# Interconnect_board_v1p2.net
KiCad netlist of a schematic drawn in EAGLE
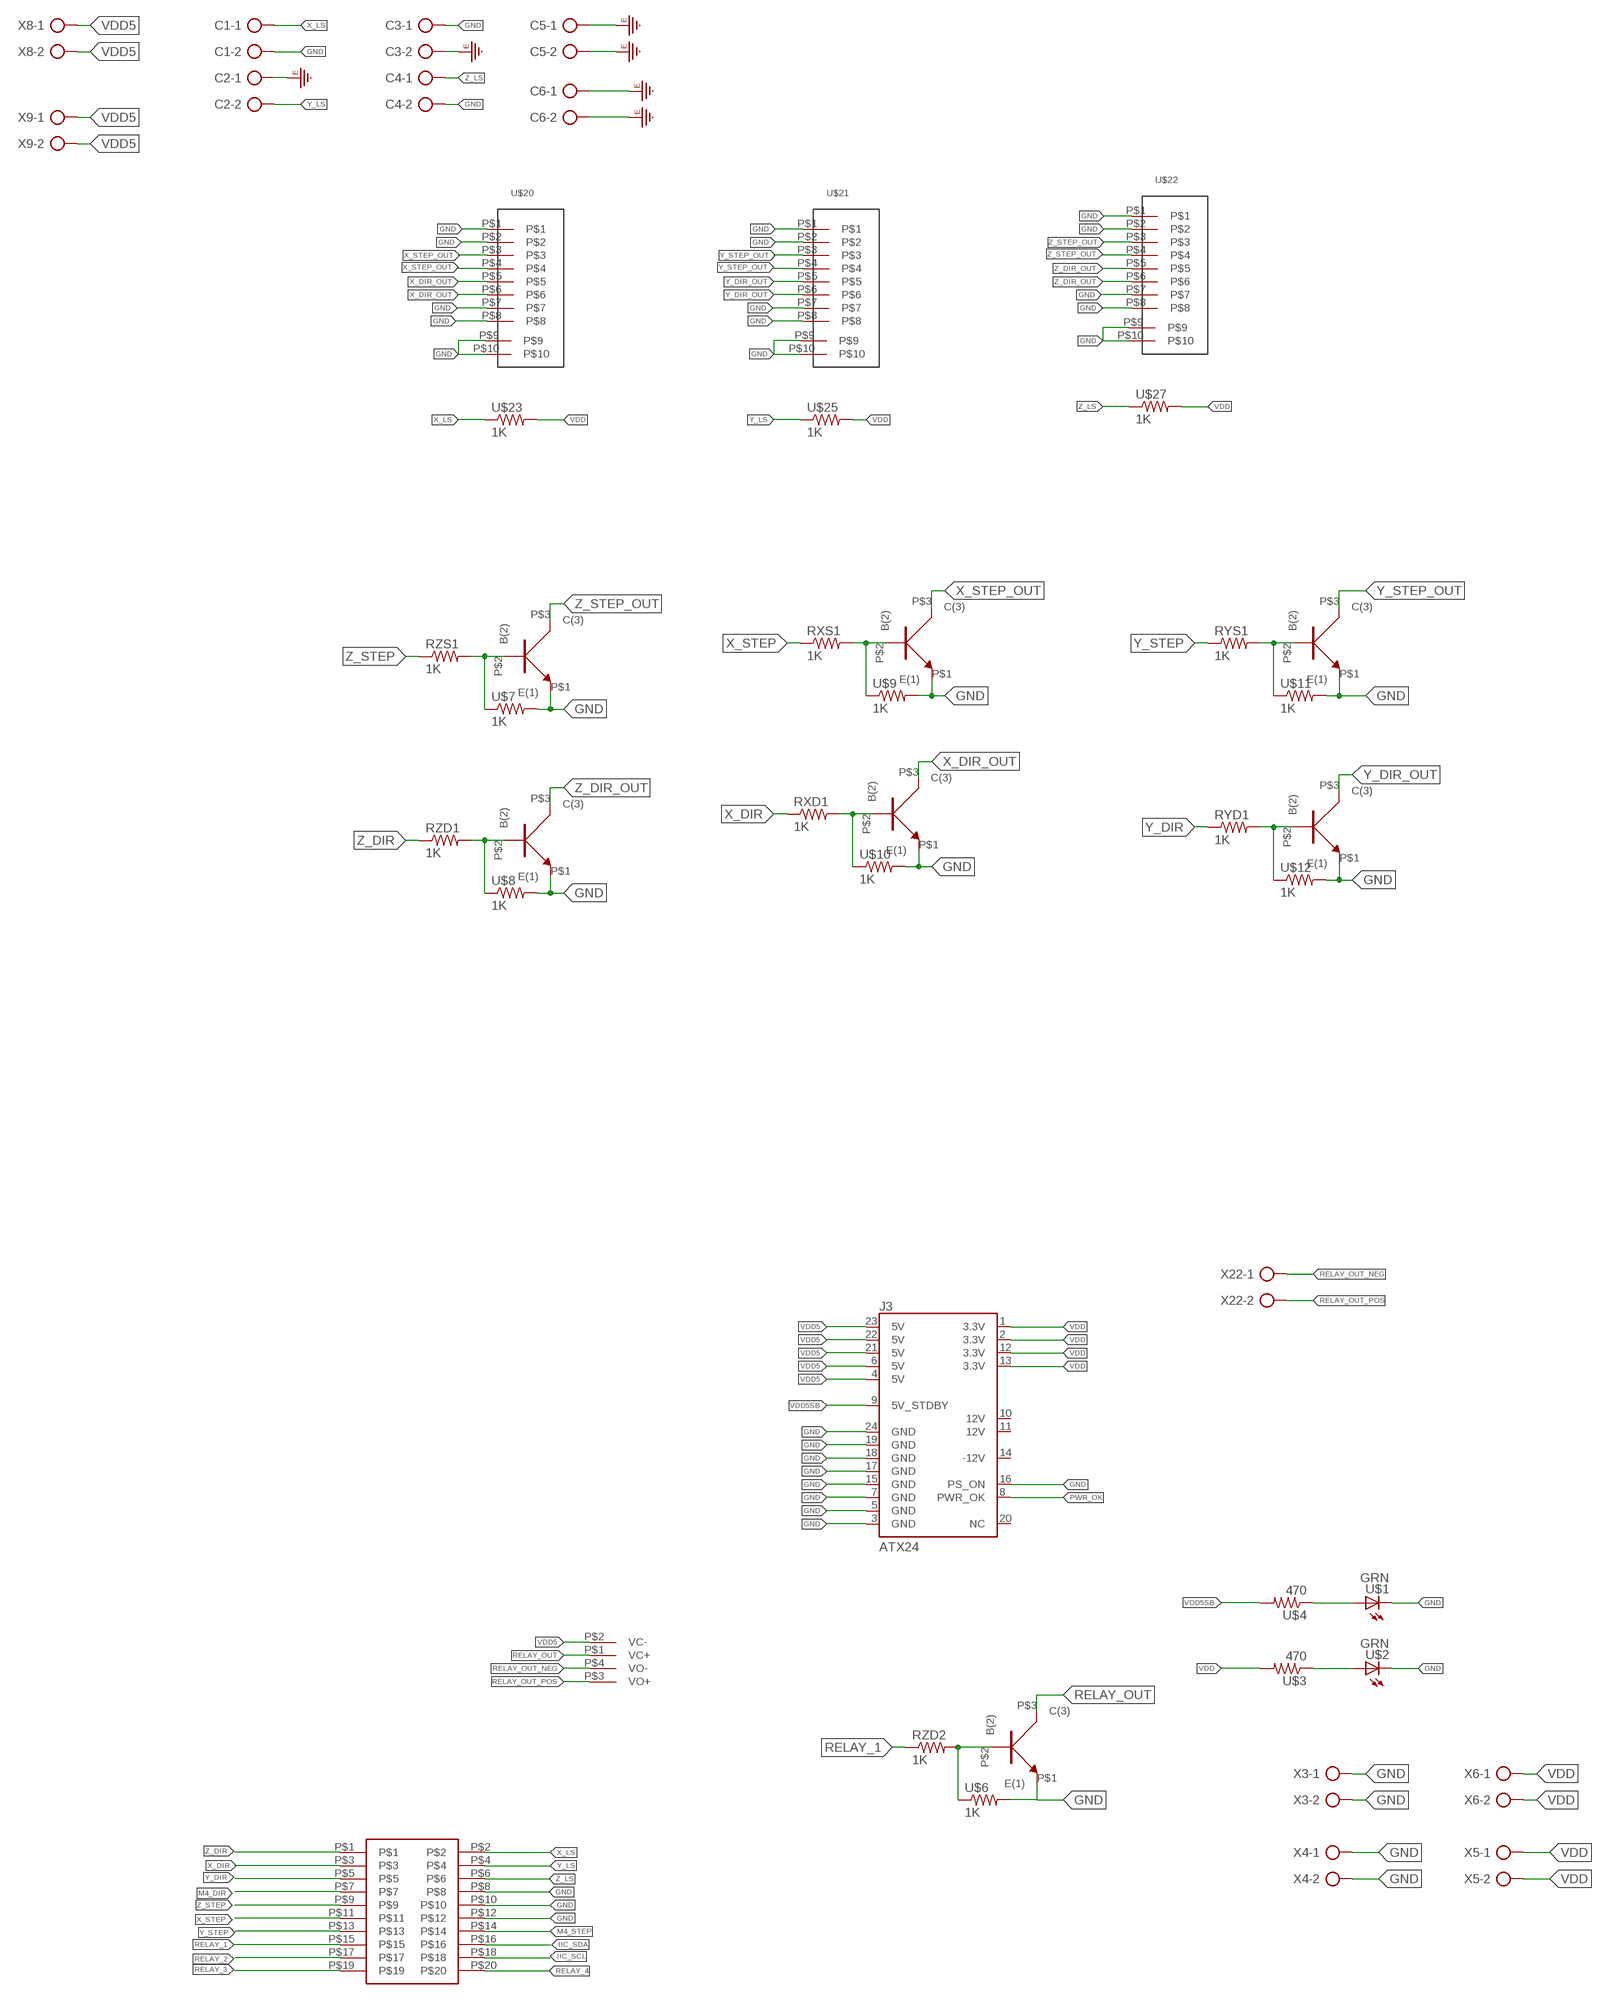
[diagram p0: schematic, sheet 1]

(export (version "E")
  (design (tool "Eeschema 10.0.6"))
  (components
    (comp (ref "C1")
      (value "AK300/2")
      (footprint "eagle-import:AK300_2")
      (libsource (lib "eagle-import") (part "AK300/2"))
    )
    (comp (ref "C2")
      (value "AK300/2")
      (footprint "eagle-import:AK300_2")
      (libsource (lib "eagle-import") (part "AK300/2"))
    )
    (comp (ref "C3")
      (value "AK300/2")
      (footprint "eagle-import:AK300_2")
      (libsource (lib "eagle-import") (part "AK300/2"))
    )
    (comp (ref "C4")
      (value "AK300/2")
      (footprint "eagle-import:AK300_2")
      (libsource (lib "eagle-import") (part "AK300/2"))
    )
    (comp (ref "C5")
      (value "AK300/2")
      (footprint "eagle-import:AK300_2")
      (libsource (lib "eagle-import") (part "AK300/2"))
    )
    (comp (ref "C6")
      (value "AK300/2")
      (footprint "eagle-import:AK300_2")
      (libsource (lib "eagle-import") (part "AK300/2"))
    )
    (comp (ref "J3")
      (value "ATX24")
      (footprint "eagle-import:ATX24_STRAIGHT")
      (libsource (lib "eagle-import") (part "ATX24"))
    )
    (comp (ref "RXD1")
      (value "R_0805_1K")
      (footprint "eagle-import:R_0805_1K")
      (libsource (lib "eagle-import") (part "R_0805_1K"))
    )
    (comp (ref "RXS1")
      (value "R_0805_1K")
      (footprint "eagle-import:R_0805_1K")
      (libsource (lib "eagle-import") (part "R_0805_1K"))
    )
    (comp (ref "RYD1")
      (value "R_0805_1K")
      (footprint "eagle-import:R_0805_1K")
      (libsource (lib "eagle-import") (part "R_0805_1K"))
    )
    (comp (ref "RYS1")
      (value "R_0805_1K")
      (footprint "eagle-import:R_0805_1K")
      (libsource (lib "eagle-import") (part "R_0805_1K"))
    )
    (comp (ref "RZD1")
      (value "R_0805_1K")
      (footprint "eagle-import:R_0805_1K")
      (libsource (lib "eagle-import") (part "R_0805_1K"))
    )
    (comp (ref "RZD2")
      (value "R_0805_1K")
      (footprint "eagle-import:R_0805_1K")
      (libsource (lib "eagle-import") (part "R_0805_1K"))
    )
    (comp (ref "RZS1")
      (value "R_0805_1K")
      (footprint "eagle-import:R_0805_1K")
      (libsource (lib "eagle-import") (part "R_0805_1K"))
    )
    (comp (ref "U$1")
      (value "LED_0805_GREEN")
      (footprint "eagle-import:LED_0805_GREEN")
      (libsource (lib "eagle-import") (part "LED_0805_GREEN"))
    )
    (comp (ref "U$2")
      (value "LED_0805_GREEN")
      (footprint "eagle-import:LED_0805_GREEN")
      (libsource (lib "eagle-import") (part "LED_0805_GREEN"))
    )
    (comp (ref "U$3")
      (value "R_0805_470")
      (footprint "eagle-import:R_0805_470")
      (libsource (lib "eagle-import") (part "R_0805_470"))
    )
    (comp (ref "U$4")
      (value "R_0805_470")
      (footprint "eagle-import:R_0805_470")
      (libsource (lib "eagle-import") (part "R_0805_470"))
    )
    (comp (ref "U$5")
      (value "RELAY_KYOTO_KF0604D")
      (footprint "eagle-import:RELAY_KYOTO_KF0604D")
      (libsource (lib "eagle-import") (part "RELAY_KYOTO_KF0604D"))
    )
    (comp (ref "U$6")
      (value "R_0805_1K")
      (footprint "eagle-import:R_0805_1K")
      (libsource (lib "eagle-import") (part "R_0805_1K"))
    )
    (comp (ref "U$7")
      (value "R_0805_1K")
      (footprint "eagle-import:R_0805_1K")
      (libsource (lib "eagle-import") (part "R_0805_1K"))
    )
    (comp (ref "U$8")
      (value "R_0805_1K")
      (footprint "eagle-import:R_0805_1K")
      (libsource (lib "eagle-import") (part "R_0805_1K"))
    )
    (comp (ref "U$9")
      (value "R_0805_1K")
      (footprint "eagle-import:R_0805_1K")
      (libsource (lib "eagle-import") (part "R_0805_1K"))
    )
    (comp (ref "U$10")
      (value "R_0805_1K")
      (footprint "eagle-import:R_0805_1K")
      (libsource (lib "eagle-import") (part "R_0805_1K"))
    )
    (comp (ref "U$11")
      (value "R_0805_1K")
      (footprint "eagle-import:R_0805_1K")
      (libsource (lib "eagle-import") (part "R_0805_1K"))
    )
    (comp (ref "U$12")
      (value "R_0805_1K")
      (footprint "eagle-import:R_0805_1K")
      (libsource (lib "eagle-import") (part "R_0805_1K"))
    )
    (comp (ref "U$13")
      (value "TRANS_NPN")
      (footprint "eagle-import:TO_92_STRAIGHT")
      (libsource (lib "eagle-import") (part "TRANS_NPN"))
    )
    (comp (ref "U$14")
      (value "TRANS_NPN")
      (footprint "eagle-import:TO_92_STRAIGHT")
      (libsource (lib "eagle-import") (part "TRANS_NPN"))
    )
    (comp (ref "U$15")
      (value "TRANS_NPN")
      (footprint "eagle-import:TO_92_STRAIGHT")
      (libsource (lib "eagle-import") (part "TRANS_NPN"))
    )
    (comp (ref "U$16")
      (value "TRANS_NPN")
      (footprint "eagle-import:TO_92_STRAIGHT")
      (libsource (lib "eagle-import") (part "TRANS_NPN"))
    )
    (comp (ref "U$17")
      (value "TRANS_NPN")
      (footprint "eagle-import:TO_92_STRAIGHT")
      (libsource (lib "eagle-import") (part "TRANS_NPN"))
    )
    (comp (ref "U$18")
      (value "TRANS_NPN")
      (footprint "eagle-import:TO_92_STRAIGHT")
      (libsource (lib "eagle-import") (part "TRANS_NPN"))
    )
    (comp (ref "U$19")
      (value "TRANS_NPN")
      (footprint "eagle-import:TO_92_STRAIGHT")
      (libsource (lib "eagle-import") (part "TRANS_NPN"))
    )
    (comp (ref "U$20")
      (value "RJ45_SMTRJ")
      (footprint "eagle-import:RJ45_SMT")
      (libsource (lib "eagle-import") (part "RJ45_SMTRJ"))
    )
    (comp (ref "U$21")
      (value "RJ45_SMTRJ")
      (footprint "eagle-import:RJ45_SMT")
      (libsource (lib "eagle-import") (part "RJ45_SMTRJ"))
    )
    (comp (ref "U$22")
      (value "RJ45_SMTRJ")
      (footprint "eagle-import:RJ45_SMT")
      (libsource (lib "eagle-import") (part "RJ45_SMTRJ"))
    )
    (comp (ref "U$23")
      (value "R_0805_1K")
      (footprint "eagle-import:R_0805_1K")
      (libsource (lib "eagle-import") (part "R_0805_1K"))
    )
    (comp (ref "U$25")
      (value "R_0805_1K")
      (footprint "eagle-import:R_0805_1K")
      (libsource (lib "eagle-import") (part "R_0805_1K"))
    )
    (comp (ref "U$26")
      (value "2_X_10_HEADER_GENERIC")
      (footprint "eagle-import:2_X_10_.1_INCH")
      (libsource (lib "eagle-import") (part "2_X_10_HEADER_GENERIC"))
    )
    (comp (ref "U$27")
      (value "R_0805_1K")
      (footprint "eagle-import:R_0805_1K")
      (libsource (lib "eagle-import") (part "R_0805_1K"))
    )
    (comp (ref "X3")
      (value "AK300/2")
      (footprint "eagle-import:AK300_2")
      (libsource (lib "eagle-import") (part "AK300/2"))
    )
    (comp (ref "X4")
      (value "AK300/2")
      (footprint "eagle-import:AK300_2")
      (libsource (lib "eagle-import") (part "AK300/2"))
    )
    (comp (ref "X5")
      (value "AK300/2")
      (footprint "eagle-import:AK300_2")
      (libsource (lib "eagle-import") (part "AK300/2"))
    )
    (comp (ref "X6")
      (value "AK300/2")
      (footprint "eagle-import:AK300_2")
      (libsource (lib "eagle-import") (part "AK300/2"))
    )
    (comp (ref "X8")
      (value "AK300/2")
      (footprint "eagle-import:AK300_2")
      (libsource (lib "eagle-import") (part "AK300/2"))
    )
    (comp (ref "X9")
      (value "AK300/2")
      (footprint "eagle-import:AK300_2")
      (libsource (lib "eagle-import") (part "AK300/2"))
    )
    (comp (ref "X22")
      (value "AK300/2")
      (footprint "eagle-import:AK300_2")
      (libsource (lib "eagle-import") (part "AK300/2"))
    )
  )
  (nets
    (net (code "1") (name "GND") (class "Default")
      (node (ref "C1") (pin "2") (pinfunction "KL_2") (pintype "passive"))
      (node (ref "C3") (pin "1") (pinfunction "KL_1") (pintype "passive"))
      (node (ref "C4") (pin "2") (pinfunction "KL_2") (pintype "passive"))
      (node (ref "J3") (pin "15") (pinfunction "GND_15") (pintype "bidirectional"))
      (node (ref "J3") (pin "16") (pinfunction "PS_ON_16") (pintype "bidirectional"))
      (node (ref "J3") (pin "17") (pinfunction "GND_17") (pintype "bidirectional"))
      (node (ref "J3") (pin "18") (pinfunction "GND_18") (pintype "bidirectional"))
      (node (ref "J3") (pin "19") (pinfunction "GND_19") (pintype "bidirectional"))
      (node (ref "J3") (pin "24") (pinfunction "GND_24") (pintype "bidirectional"))
      (node (ref "J3") (pin "3") (pinfunction "GND_3") (pintype "bidirectional"))
      (node (ref "J3") (pin "5") (pinfunction "GND_5") (pintype "bidirectional"))
      (node (ref "J3") (pin "7") (pinfunction "GND_7") (pintype "bidirectional"))
      (node (ref "U$1") (pin "C") (pinfunction "C_C") (pintype "passive"))
      (node (ref "U$10") (pin "2") (pinfunction "2_2") (pintype "passive"))
      (node (ref "U$11") (pin "2") (pinfunction "2_2") (pintype "passive"))
      (node (ref "U$12") (pin "2") (pinfunction "2_2") (pintype "passive"))
      (node (ref "U$13") (pin "P$1") (pinfunction "E(1)_P$1") (pintype "output"))
      (node (ref "U$14") (pin "P$1") (pinfunction "E(1)_P$1") (pintype "output"))
      (node (ref "U$15") (pin "P$1") (pinfunction "E(1)_P$1") (pintype "output"))
      (node (ref "U$16") (pin "P$1") (pinfunction "E(1)_P$1") (pintype "output"))
      (node (ref "U$17") (pin "P$1") (pinfunction "E(1)_P$1") (pintype "output"))
      (node (ref "U$18") (pin "P$1") (pinfunction "E(1)_P$1") (pintype "output"))
      (node (ref "U$19") (pin "P$1") (pinfunction "E(1)_P$1") (pintype "output"))
      (node (ref "U$2") (pin "C") (pinfunction "C_C") (pintype "passive"))
      (node (ref "U$20") (pin "P$1") (pinfunction "P$1_P$1") (pintype "bidirectional"))
      (node (ref "U$20") (pin "P$10") (pinfunction "P$10_P$10") (pintype "bidirectional"))
      (node (ref "U$20") (pin "P$2") (pinfunction "P$2_P$2") (pintype "bidirectional"))
      (node (ref "U$20") (pin "P$7") (pinfunction "P$7_P$7") (pintype "bidirectional"))
      (node (ref "U$20") (pin "P$8") (pinfunction "P$8_P$8") (pintype "bidirectional"))
      (node (ref "U$20") (pin "P$9") (pinfunction "P$9_P$9") (pintype "bidirectional"))
      (node (ref "U$21") (pin "P$1") (pinfunction "P$1_P$1") (pintype "bidirectional"))
      (node (ref "U$21") (pin "P$10") (pinfunction "P$10_P$10") (pintype "bidirectional"))
      (node (ref "U$21") (pin "P$2") (pinfunction "P$2_P$2") (pintype "bidirectional"))
      (node (ref "U$21") (pin "P$7") (pinfunction "P$7_P$7") (pintype "bidirectional"))
      (node (ref "U$21") (pin "P$8") (pinfunction "P$8_P$8") (pintype "bidirectional"))
      (node (ref "U$21") (pin "P$9") (pinfunction "P$9_P$9") (pintype "bidirectional"))
      (node (ref "U$22") (pin "P$1") (pinfunction "P$1_P$1") (pintype "bidirectional"))
      (node (ref "U$22") (pin "P$10") (pinfunction "P$10_P$10") (pintype "bidirectional"))
      (node (ref "U$22") (pin "P$2") (pinfunction "P$2_P$2") (pintype "bidirectional"))
      (node (ref "U$22") (pin "P$7") (pinfunction "P$7_P$7") (pintype "bidirectional"))
      (node (ref "U$22") (pin "P$8") (pinfunction "P$8_P$8") (pintype "bidirectional"))
      (node (ref "U$22") (pin "P$9") (pinfunction "P$9_P$9") (pintype "bidirectional"))
      (node (ref "U$26") (pin "P$10") (pinfunction "P$10_P$10") (pintype "bidirectional"))
      (node (ref "U$26") (pin "P$12") (pinfunction "P$12_P$12") (pintype "bidirectional"))
      (node (ref "U$26") (pin "P$8") (pinfunction "P$8_P$8") (pintype "bidirectional"))
      (node (ref "U$6") (pin "2") (pinfunction "2_2") (pintype "passive"))
      (node (ref "U$7") (pin "2") (pinfunction "2_2") (pintype "passive"))
      (node (ref "U$8") (pin "2") (pinfunction "2_2") (pintype "passive"))
      (node (ref "U$9") (pin "2") (pinfunction "2_2") (pintype "passive"))
      (node (ref "X3") (pin "1") (pinfunction "KL_1") (pintype "passive"))
      (node (ref "X3") (pin "2") (pinfunction "KL_2") (pintype "passive"))
      (node (ref "X4") (pin "1") (pinfunction "KL_1") (pintype "passive"))
      (node (ref "X4") (pin "2") (pinfunction "KL_2") (pintype "passive"))
    )
    (net (code "2") (name "GNDEARTH") (class "Default")
      (node (ref "C2") (pin "1") (pinfunction "KL_1") (pintype "passive"))
      (node (ref "C3") (pin "2") (pinfunction "KL_2") (pintype "passive"))
      (node (ref "C5") (pin "1") (pinfunction "KL_1") (pintype "passive"))
      (node (ref "C5") (pin "2") (pinfunction "KL_2") (pintype "passive"))
      (node (ref "C6") (pin "1") (pinfunction "KL_1") (pintype "passive"))
      (node (ref "C6") (pin "2") (pinfunction "KL_2") (pintype "passive"))
    )
    (net (code "3") (name "IIC_SCL") (class "Default")
      (node (ref "U$26") (pin "P$18") (pinfunction "P$18_P$18") (pintype "bidirectional"))
    )
    (net (code "4") (name "IIC_SDA") (class "Default")
      (node (ref "U$26") (pin "P$16") (pinfunction "P$16_P$16") (pintype "bidirectional"))
    )
    (net (code "5") (name "M4_DIR") (class "Default")
      (node (ref "U$26") (pin "P$7") (pinfunction "P$7_P$7") (pintype "bidirectional"))
    )
    (net (code "6") (name "M4_STEP") (class "Default")
      (node (ref "U$26") (pin "P$14") (pinfunction "P$14_P$14") (pintype "bidirectional"))
    )
    (net (code "7") (name "Net-(U$1-PadA)") (class "Default")
      (node (ref "U$1") (pin "A") (pinfunction "A_A") (pintype "passive"))
      (node (ref "U$4") (pin "1") (pinfunction "1_1") (pintype "passive"))
    )
    (net (code "8") (name "Net-(U$2-PadA)") (class "Default")
      (node (ref "U$2") (pin "A") (pinfunction "A_A") (pintype "passive"))
      (node (ref "U$3") (pin "1") (pinfunction "1_1") (pintype "passive"))
    )
    (net (code "9") (name "Net-(U$13-B(2))") (class "Default")
      (node (ref "RZS1") (pin "2") (pinfunction "2_2") (pintype "passive"))
      (node (ref "U$13") (pin "P$2") (pinfunction "B(2)_P$2") (pintype "input"))
      (node (ref "U$7") (pin "1") (pinfunction "1_1") (pintype "passive"))
    )
    (net (code "10") (name "Net-(U$14-B(2))") (class "Default")
      (node (ref "RZD1") (pin "2") (pinfunction "2_2") (pintype "passive"))
      (node (ref "U$14") (pin "P$2") (pinfunction "B(2)_P$2") (pintype "input"))
      (node (ref "U$8") (pin "1") (pinfunction "1_1") (pintype "passive"))
    )
    (net (code "11") (name "Net-(U$15-B(2))") (class "Default")
      (node (ref "RXS1") (pin "2") (pinfunction "2_2") (pintype "passive"))
      (node (ref "U$15") (pin "P$2") (pinfunction "B(2)_P$2") (pintype "input"))
      (node (ref "U$9") (pin "1") (pinfunction "1_1") (pintype "passive"))
    )
    (net (code "12") (name "Net-(U$16-B(2))") (class "Default")
      (node (ref "RXD1") (pin "2") (pinfunction "2_2") (pintype "passive"))
      (node (ref "U$10") (pin "1") (pinfunction "1_1") (pintype "passive"))
      (node (ref "U$16") (pin "P$2") (pinfunction "B(2)_P$2") (pintype "input"))
    )
    (net (code "13") (name "Net-(U$17-B(2))") (class "Default")
      (node (ref "RYD1") (pin "2") (pinfunction "2_2") (pintype "passive"))
      (node (ref "U$12") (pin "1") (pinfunction "1_1") (pintype "passive"))
      (node (ref "U$17") (pin "P$2") (pinfunction "B(2)_P$2") (pintype "input"))
    )
    (net (code "14") (name "Net-(U$18-B(2))") (class "Default")
      (node (ref "RYS1") (pin "2") (pinfunction "2_2") (pintype "passive"))
      (node (ref "U$11") (pin "1") (pinfunction "1_1") (pintype "passive"))
      (node (ref "U$18") (pin "P$2") (pinfunction "B(2)_P$2") (pintype "input"))
    )
    (net (code "15") (name "Net-(U$19-B(2))") (class "Default")
      (node (ref "RZD2") (pin "2") (pinfunction "2_2") (pintype "passive"))
      (node (ref "U$19") (pin "P$2") (pinfunction "B(2)_P$2") (pintype "input"))
      (node (ref "U$6") (pin "1") (pinfunction "1_1") (pintype "passive"))
    )
    (net (code "16") (name "PWR_OK") (class "Default")
      (node (ref "J3") (pin "8") (pinfunction "PWR_OK_8") (pintype "bidirectional"))
    )
    (net (code "17") (name "RELAY_1") (class "Default")
      (node (ref "RZD2") (pin "1") (pinfunction "1_1") (pintype "passive"))
      (node (ref "U$26") (pin "P$15") (pinfunction "P$15_P$15") (pintype "bidirectional"))
    )
    (net (code "18") (name "RELAY_2") (class "Default")
      (node (ref "U$26") (pin "P$17") (pinfunction "P$17_P$17") (pintype "bidirectional"))
    )
    (net (code "19") (name "RELAY_3") (class "Default")
      (node (ref "U$26") (pin "P$19") (pinfunction "P$19_P$19") (pintype "bidirectional"))
    )
    (net (code "20") (name "RELAY_4") (class "Default")
      (node (ref "U$26") (pin "P$20") (pinfunction "P$20_P$20") (pintype "bidirectional"))
    )
    (net (code "21") (name "RELAY_OUT") (class "Default")
      (node (ref "U$19") (pin "P$3") (pinfunction "C(3)_P$3") (pintype "input"))
      (node (ref "U$5") (pin "P$1") (pinfunction "VC+_P$1") (pintype "bidirectional"))
    )
    (net (code "22") (name "RELAY_OUT_NEG") (class "Default")
      (node (ref "U$5") (pin "P$4") (pinfunction "VO-_P$4") (pintype "bidirectional"))
      (node (ref "X22") (pin "1") (pinfunction "KL_1") (pintype "passive"))
    )
    (net (code "23") (name "RELAY_OUT_POS") (class "Default")
      (node (ref "U$5") (pin "P$3") (pinfunction "VO+_P$3") (pintype "bidirectional"))
      (node (ref "X22") (pin "2") (pinfunction "KL_2") (pintype "passive"))
    )
    (net (code "24") (name "VDD") (class "Default")
      (node (ref "J3") (pin "1") (pinfunction "3.3V_1") (pintype "bidirectional"))
      (node (ref "J3") (pin "12") (pinfunction "3.3V_12") (pintype "bidirectional"))
      (node (ref "J3") (pin "13") (pinfunction "3.3V_13") (pintype "bidirectional"))
      (node (ref "J3") (pin "2") (pinfunction "3.3V_2") (pintype "bidirectional"))
      (node (ref "U$23") (pin "2") (pinfunction "2_2") (pintype "passive"))
      (node (ref "U$25") (pin "2") (pinfunction "2_2") (pintype "passive"))
      (node (ref "U$27") (pin "2") (pinfunction "2_2") (pintype "passive"))
      (node (ref "U$3") (pin "2") (pinfunction "2_2") (pintype "passive"))
      (node (ref "X5") (pin "1") (pinfunction "KL_1") (pintype "passive"))
      (node (ref "X5") (pin "2") (pinfunction "KL_2") (pintype "passive"))
      (node (ref "X6") (pin "1") (pinfunction "KL_1") (pintype "passive"))
      (node (ref "X6") (pin "2") (pinfunction "KL_2") (pintype "passive"))
    )
    (net (code "25") (name "VDD5") (class "Default")
      (node (ref "J3") (pin "21") (pinfunction "5V_21") (pintype "bidirectional"))
      (node (ref "J3") (pin "22") (pinfunction "5V_22") (pintype "bidirectional"))
      (node (ref "J3") (pin "23") (pinfunction "5V_23") (pintype "bidirectional"))
      (node (ref "J3") (pin "4") (pinfunction "5V_4") (pintype "bidirectional"))
      (node (ref "J3") (pin "6") (pinfunction "5V_6") (pintype "bidirectional"))
      (node (ref "U$5") (pin "P$2") (pinfunction "VC-_P$2") (pintype "bidirectional"))
      (node (ref "X8") (pin "1") (pinfunction "KL_1") (pintype "passive"))
      (node (ref "X8") (pin "2") (pinfunction "KL_2") (pintype "passive"))
      (node (ref "X9") (pin "1") (pinfunction "KL_1") (pintype "passive"))
      (node (ref "X9") (pin "2") (pinfunction "KL_2") (pintype "passive"))
    )
    (net (code "26") (name "VDD5SB") (class "Default")
      (node (ref "J3") (pin "9") (pinfunction "5V_STDBY_9") (pintype "bidirectional"))
      (node (ref "U$4") (pin "2") (pinfunction "2_2") (pintype "passive"))
    )
    (net (code "27") (name "X_DIR") (class "Default")
      (node (ref "RXD1") (pin "1") (pinfunction "1_1") (pintype "passive"))
      (node (ref "U$26") (pin "P$3") (pinfunction "P$3_P$3") (pintype "bidirectional"))
    )
    (net (code "28") (name "X_DIR_OUT") (class "Default")
      (node (ref "U$16") (pin "P$3") (pinfunction "C(3)_P$3") (pintype "input"))
      (node (ref "U$20") (pin "P$5") (pinfunction "P$5_P$5") (pintype "bidirectional"))
      (node (ref "U$20") (pin "P$6") (pinfunction "P$6_P$6") (pintype "bidirectional"))
    )
    (net (code "29") (name "X_LS") (class "Default")
      (node (ref "C1") (pin "1") (pinfunction "KL_1") (pintype "passive"))
      (node (ref "U$23") (pin "1") (pinfunction "1_1") (pintype "passive"))
      (node (ref "U$26") (pin "P$2") (pinfunction "P$2_P$2") (pintype "bidirectional"))
    )
    (net (code "30") (name "X_STEP") (class "Default")
      (node (ref "RXS1") (pin "1") (pinfunction "1_1") (pintype "passive"))
      (node (ref "U$26") (pin "P$11") (pinfunction "P$11_P$11") (pintype "bidirectional"))
    )
    (net (code "31") (name "X_STEP_OUT") (class "Default")
      (node (ref "U$15") (pin "P$3") (pinfunction "C(3)_P$3") (pintype "input"))
      (node (ref "U$20") (pin "P$3") (pinfunction "P$3_P$3") (pintype "bidirectional"))
      (node (ref "U$20") (pin "P$4") (pinfunction "P$4_P$4") (pintype "bidirectional"))
    )
    (net (code "32") (name "Y_DIR") (class "Default")
      (node (ref "RYD1") (pin "1") (pinfunction "1_1") (pintype "passive"))
      (node (ref "U$26") (pin "P$5") (pinfunction "P$5_P$5") (pintype "bidirectional"))
    )
    (net (code "33") (name "Y_DIR_OUT") (class "Default")
      (node (ref "U$17") (pin "P$3") (pinfunction "C(3)_P$3") (pintype "input"))
      (node (ref "U$21") (pin "P$5") (pinfunction "P$5_P$5") (pintype "bidirectional"))
      (node (ref "U$21") (pin "P$6") (pinfunction "P$6_P$6") (pintype "bidirectional"))
    )
    (net (code "34") (name "Y_LS") (class "Default")
      (node (ref "C2") (pin "2") (pinfunction "KL_2") (pintype "passive"))
      (node (ref "U$25") (pin "1") (pinfunction "1_1") (pintype "passive"))
      (node (ref "U$26") (pin "P$4") (pinfunction "P$4_P$4") (pintype "bidirectional"))
    )
    (net (code "35") (name "Y_STEP") (class "Default")
      (node (ref "RYS1") (pin "1") (pinfunction "1_1") (pintype "passive"))
      (node (ref "U$26") (pin "P$13") (pinfunction "P$13_P$13") (pintype "bidirectional"))
    )
    (net (code "36") (name "Y_STEP_OUT") (class "Default")
      (node (ref "U$18") (pin "P$3") (pinfunction "C(3)_P$3") (pintype "input"))
      (node (ref "U$21") (pin "P$3") (pinfunction "P$3_P$3") (pintype "bidirectional"))
      (node (ref "U$21") (pin "P$4") (pinfunction "P$4_P$4") (pintype "bidirectional"))
    )
    (net (code "37") (name "Z_DIR") (class "Default")
      (node (ref "RZD1") (pin "1") (pinfunction "1_1") (pintype "passive"))
      (node (ref "U$26") (pin "P$1") (pinfunction "P$1_P$1") (pintype "bidirectional"))
    )
    (net (code "38") (name "Z_DIR_OUT") (class "Default")
      (node (ref "U$14") (pin "P$3") (pinfunction "C(3)_P$3") (pintype "input"))
      (node (ref "U$22") (pin "P$5") (pinfunction "P$5_P$5") (pintype "bidirectional"))
      (node (ref "U$22") (pin "P$6") (pinfunction "P$6_P$6") (pintype "bidirectional"))
    )
    (net (code "39") (name "Z_LS") (class "Default")
      (node (ref "C4") (pin "1") (pinfunction "KL_1") (pintype "passive"))
      (node (ref "U$26") (pin "P$6") (pinfunction "P$6_P$6") (pintype "bidirectional"))
      (node (ref "U$27") (pin "1") (pinfunction "1_1") (pintype "passive"))
    )
    (net (code "40") (name "Z_STEP") (class "Default")
      (node (ref "RZS1") (pin "1") (pinfunction "1_1") (pintype "passive"))
      (node (ref "U$26") (pin "P$9") (pinfunction "P$9_P$9") (pintype "bidirectional"))
    )
    (net (code "41") (name "Z_STEP_OUT") (class "Default")
      (node (ref "U$13") (pin "P$3") (pinfunction "C(3)_P$3") (pintype "input"))
      (node (ref "U$22") (pin "P$3") (pinfunction "P$3_P$3") (pintype "bidirectional"))
      (node (ref "U$22") (pin "P$4") (pinfunction "P$4_P$4") (pintype "bidirectional"))
    )
    (net (code "42") (name "unconnected-(J3--12V-Pad14)") (class "Default")
      (node (ref "J3") (pin "14") (pinfunction "-12V_14") (pintype "bidirectional"))
    )
    (net (code "43") (name "unconnected-(J3-12V-Pad10)") (class "Default")
      (node (ref "J3") (pin "10") (pinfunction "12V_10") (pintype "bidirectional"))
    )
    (net (code "44") (name "unconnected-(J3-12V-Pad11)") (class "Default")
      (node (ref "J3") (pin "11") (pinfunction "12V_11") (pintype "bidirectional"))
    )
    (net (code "45") (name "unconnected-(J3-NC-Pad20)") (class "Default")
      (node (ref "J3") (pin "20") (pinfunction "NC_20") (pintype "bidirectional"))
    )
  )
)
